# IR_BLASTER_MINI.net
KiCad netlist of a schematic drawn in EAGLE
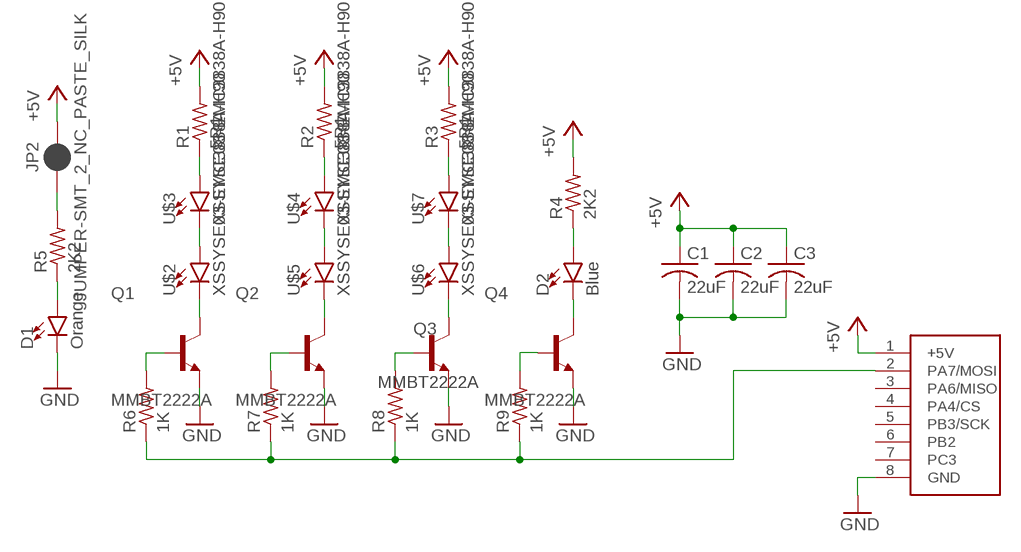
[diagram p0: schematic, sheet 1]

(export (version "E")
  (design (tool "Eeschema 10.0.6"))
  (components
    (comp (ref "C1")
      (value "22uF")
      (footprint "eagle-import:C3216")
      (libsource (lib "eagle-import") (part "C-USC3216"))
    )
    (comp (ref "C2")
      (value "22uF")
      (footprint "eagle-import:C3216")
      (libsource (lib "eagle-import") (part "C-USC3216"))
    )
    (comp (ref "C3")
      (value "22uF")
      (footprint "eagle-import:C3216")
      (libsource (lib "eagle-import") (part "C-USC3216"))
    )
    (comp (ref "D1")
      (value "Orange")
      (footprint "eagle-import:LED-0603")
      (libsource (lib "eagle-import") (part "LED-GREEN0603"))
    )
    (comp (ref "D2")
      (value "Blue")
      (footprint "eagle-import:LED-0603")
      (libsource (lib "eagle-import") (part "LED-BLUE0603"))
    )
    (comp (ref "JP2")
      (value "JUMPER-SMT_2_NC_PASTE_SILK")
      (footprint "eagle-import:SMT-JUMPER_2_NC_PASTE_SILK")
      (libsource (lib "eagle-import") (part "JUMPER-SMT_2_NC_PASTE_SILK"))
    )
    (comp (ref "Q1")
      (value "MMBT2222A")
      (footprint "eagle-import:SOT95P240X120-3N")
      (fields (field (name "MANUFACTURER") "Diotec"))
      (libsource (lib "eagle-import") (part "MMBT2222A"))
    )
    (comp (ref "Q2")
      (value "MMBT2222A")
      (footprint "eagle-import:SOT95P240X120-3N")
      (fields (field (name "MANUFACTURER") "Diotec"))
      (libsource (lib "eagle-import") (part "MMBT2222A"))
    )
    (comp (ref "Q3")
      (value "MMBT2222A")
      (footprint "eagle-import:SOT95P240X120-3N")
      (fields (field (name "MANUFACTURER") "Diotec"))
      (libsource (lib "eagle-import") (part "MMBT2222A"))
    )
    (comp (ref "Q4")
      (value "MMBT2222A")
      (footprint "eagle-import:SOT95P240X120-3N")
      (fields (field (name "MANUFACTURER") "Diotec"))
      (libsource (lib "eagle-import") (part "MMBT2222A"))
    )
    (comp (ref "R1")
      (value "5R1")
      (footprint "eagle-import:R2512")
      (libsource (lib "eagle-import") (part "R-US_R2512"))
    )
    (comp (ref "R2")
      (value "5R1")
      (footprint "eagle-import:R2512")
      (libsource (lib "eagle-import") (part "R-US_R2512"))
    )
    (comp (ref "R3")
      (value "5R1")
      (footprint "eagle-import:R2512")
      (libsource (lib "eagle-import") (part "R-US_R2512"))
    )
    (comp (ref "R4")
      (value "2K2")
      (footprint "eagle-import:R0603")
      (libsource (lib "eagle-import") (part "R-US_R0603"))
    )
    (comp (ref "R5")
      (value "2K2")
      (footprint "eagle-import:R0603")
      (libsource (lib "eagle-import") (part "R-US_R0603"))
    )
    (comp (ref "R6")
      (value "1K")
      (footprint "eagle-import:R0603")
      (libsource (lib "eagle-import") (part "R-US_R0603"))
    )
    (comp (ref "R7")
      (value "1K")
      (footprint "eagle-import:R0603")
      (libsource (lib "eagle-import") (part "R-US_R0603"))
    )
    (comp (ref "R8")
      (value "1K")
      (footprint "eagle-import:R0603")
      (libsource (lib "eagle-import") (part "R-US_R0603"))
    )
    (comp (ref "R9")
      (value "1K")
      (footprint "eagle-import:R0603")
      (libsource (lib "eagle-import") (part "R-US_R0603"))
    )
    (comp (ref "U$1")
      (value "LEFT-H1-SMD")
      (footprint "eagle-import:LEFT-H1-SMD")
      (libsource (lib "eagle-import") (part "LEFT-H1-SMD"))
    )
    (comp (ref "U$2")
      (value "XSSYSE03-EMC3838A-H90")
      (footprint "eagle-import:XSSYSE03-EMC3838A-H90")
      (libsource (lib "eagle-import") (part "XSSYSE03-EMC3838A-H90"))
    )
    (comp (ref "U$3")
      (value "XSSYSE03-EMC3838A-H90")
      (footprint "eagle-import:XSSYSE03-EMC3838A-H90")
      (libsource (lib "eagle-import") (part "XSSYSE03-EMC3838A-H90"))
    )
    (comp (ref "U$4")
      (value "XSSYSE03-EMC3838A-H90")
      (footprint "eagle-import:XSSYSE03-EMC3838A-H90")
      (libsource (lib "eagle-import") (part "XSSYSE03-EMC3838A-H90"))
    )
    (comp (ref "U$5")
      (value "XSSYSE03-EMC3838A-H90")
      (footprint "eagle-import:XSSYSE03-EMC3838A-H90")
      (libsource (lib "eagle-import") (part "XSSYSE03-EMC3838A-H90"))
    )
    (comp (ref "U$6")
      (value "XSSYSE03-EMC3838A-H90")
      (footprint "eagle-import:XSSYSE03-EMC3838A-H90")
      (libsource (lib "eagle-import") (part "XSSYSE03-EMC3838A-H90"))
    )
    (comp (ref "U$7")
      (value "XSSYSE03-EMC3838A-H90")
      (footprint "eagle-import:XSSYSE03-EMC3838A-H90")
      (libsource (lib "eagle-import") (part "XSSYSE03-EMC3838A-H90"))
    )
  )
  (nets
    (net (code "1") (name "+5V") (class "Default")
      (node (ref "C1") (pin "1") (pinfunction "1_1") (pintype "passive"))
      (node (ref "C2") (pin "1") (pinfunction "1_1") (pintype "passive"))
      (node (ref "C3") (pin "1") (pinfunction "1_1") (pintype "passive"))
      (node (ref "JP2") (pin "2") (pinfunction "2_2") (pintype "passive"))
      (node (ref "R1") (pin "2") (pinfunction "2_2") (pintype "passive"))
      (node (ref "R2") (pin "2") (pinfunction "2_2") (pintype "passive"))
      (node (ref "R3") (pin "2") (pinfunction "2_2") (pintype "passive"))
      (node (ref "R4") (pin "2") (pinfunction "2_2") (pintype "passive"))
      (node (ref "U$1") (pin "1") (pinfunction "+5V_1") (pintype "bidirectional"))
    )
    (net (code "2") (name "GND") (class "Default")
      (node (ref "C1") (pin "2") (pinfunction "2_2") (pintype "passive"))
      (node (ref "C2") (pin "2") (pinfunction "2_2") (pintype "passive"))
      (node (ref "C3") (pin "2") (pinfunction "2_2") (pintype "passive"))
      (node (ref "D1") (pin "C") (pinfunction "C_C") (pintype "passive"))
      (node (ref "Q1") (pin "2") (pinfunction "E_2") (pintype "passive"))
      (node (ref "Q2") (pin "2") (pinfunction "E_2") (pintype "passive"))
      (node (ref "Q3") (pin "2") (pinfunction "E_2") (pintype "passive"))
      (node (ref "Q4") (pin "2") (pinfunction "E_2") (pintype "passive"))
      (node (ref "U$1") (pin "8") (pinfunction "GND_8") (pintype "bidirectional"))
    )
    (net (code "3") (name "Net-(D1-PadA)") (class "Default")
      (node (ref "D1") (pin "A") (pinfunction "A_A") (pintype "passive"))
      (node (ref "R5") (pin "1") (pinfunction "1_1") (pintype "passive"))
    )
    (net (code "4") (name "Net-(D2-PadA)") (class "Default")
      (node (ref "D2") (pin "A") (pinfunction "A_A") (pintype "passive"))
      (node (ref "R4") (pin "1") (pinfunction "1_1") (pintype "passive"))
    )
    (net (code "5") (name "Net-(JP2-Pad1)") (class "Default")
      (node (ref "JP2") (pin "1") (pinfunction "1_1") (pintype "passive"))
      (node (ref "R5") (pin "2") (pinfunction "2_2") (pintype "passive"))
    )
    (net (code "6") (name "Net-(Q1-B)") (class "Default")
      (node (ref "Q1") (pin "1") (pinfunction "B_1") (pintype "passive"))
      (node (ref "R6") (pin "2") (pinfunction "2_2") (pintype "passive"))
    )
    (net (code "7") (name "Net-(Q1-C)") (class "Default")
      (node (ref "Q1") (pin "3") (pinfunction "C_3") (pintype "passive"))
      (node (ref "U$2") (pin "P$2") (pinfunction "C_P$2") (pintype "passive"))
    )
    (net (code "8") (name "Net-(Q2-B)") (class "Default")
      (node (ref "Q2") (pin "1") (pinfunction "B_1") (pintype "passive"))
      (node (ref "R7") (pin "2") (pinfunction "2_2") (pintype "passive"))
    )
    (net (code "9") (name "Net-(Q2-C)") (class "Default")
      (node (ref "Q2") (pin "3") (pinfunction "C_3") (pintype "passive"))
      (node (ref "U$5") (pin "P$2") (pinfunction "C_P$2") (pintype "passive"))
    )
    (net (code "10") (name "Net-(Q3-B)") (class "Default")
      (node (ref "Q3") (pin "1") (pinfunction "B_1") (pintype "passive"))
      (node (ref "R8") (pin "2") (pinfunction "2_2") (pintype "passive"))
    )
    (net (code "11") (name "Net-(Q3-C)") (class "Default")
      (node (ref "Q3") (pin "3") (pinfunction "C_3") (pintype "passive"))
      (node (ref "U$6") (pin "P$2") (pinfunction "C_P$2") (pintype "passive"))
    )
    (net (code "12") (name "Net-(Q4-B)") (class "Default")
      (node (ref "Q4") (pin "1") (pinfunction "B_1") (pintype "passive"))
      (node (ref "R9") (pin "2") (pinfunction "2_2") (pintype "passive"))
    )
    (net (code "13") (name "Net-(Q4-C)") (class "Default")
      (node (ref "D2") (pin "C") (pinfunction "C_C") (pintype "passive"))
      (node (ref "Q4") (pin "3") (pinfunction "C_3") (pintype "passive"))
    )
    (net (code "14") (name "Net-(U$1-PA7{slash}MOSI)") (class "Default")
      (node (ref "R6") (pin "1") (pinfunction "1_1") (pintype "passive"))
      (node (ref "R7") (pin "1") (pinfunction "1_1") (pintype "passive"))
      (node (ref "R8") (pin "1") (pinfunction "1_1") (pintype "passive"))
      (node (ref "R9") (pin "1") (pinfunction "1_1") (pintype "passive"))
      (node (ref "U$1") (pin "2") (pinfunction "PA7/MOSI_2") (pintype "bidirectional"))
    )
    (net (code "15") (name "Net-(U$2-A)") (class "Default")
      (node (ref "U$2") (pin "P$1") (pinfunction "A_P$1") (pintype "passive"))
      (node (ref "U$3") (pin "P$2") (pinfunction "C_P$2") (pintype "passive"))
    )
    (net (code "16") (name "Net-(U$3-A)") (class "Default")
      (node (ref "R1") (pin "1") (pinfunction "1_1") (pintype "passive"))
      (node (ref "U$3") (pin "P$1") (pinfunction "A_P$1") (pintype "passive"))
    )
    (net (code "17") (name "Net-(U$4-A)") (class "Default")
      (node (ref "R2") (pin "1") (pinfunction "1_1") (pintype "passive"))
      (node (ref "U$4") (pin "P$1") (pinfunction "A_P$1") (pintype "passive"))
    )
    (net (code "18") (name "Net-(U$4-C)") (class "Default")
      (node (ref "U$4") (pin "P$2") (pinfunction "C_P$2") (pintype "passive"))
      (node (ref "U$5") (pin "P$1") (pinfunction "A_P$1") (pintype "passive"))
    )
    (net (code "19") (name "Net-(U$6-A)") (class "Default")
      (node (ref "U$6") (pin "P$1") (pinfunction "A_P$1") (pintype "passive"))
      (node (ref "U$7") (pin "P$2") (pinfunction "C_P$2") (pintype "passive"))
    )
    (net (code "20") (name "Net-(U$7-A)") (class "Default")
      (node (ref "R3") (pin "1") (pinfunction "1_1") (pintype "passive"))
      (node (ref "U$7") (pin "P$1") (pinfunction "A_P$1") (pintype "passive"))
    )
    (net (code "21") (name "unconnected-(U$1-PA4{slash}CS-Pad4)") (class "Default")
      (node (ref "U$1") (pin "4") (pinfunction "PA4/CS_4") (pintype "bidirectional"))
    )
    (net (code "22") (name "unconnected-(U$1-PA6{slash}MISO-Pad3)") (class "Default")
      (node (ref "U$1") (pin "3") (pinfunction "PA6/MISO_3") (pintype "bidirectional"))
    )
    (net (code "23") (name "unconnected-(U$1-PB2-Pad6)") (class "Default")
      (node (ref "U$1") (pin "6") (pinfunction "PB2_6") (pintype "bidirectional"))
    )
    (net (code "24") (name "unconnected-(U$1-PB3{slash}SCK-Pad5)") (class "Default")
      (node (ref "U$1") (pin "5") (pinfunction "PB3/SCK_5") (pintype "bidirectional"))
    )
    (net (code "25") (name "unconnected-(U$1-PC3-Pad7)") (class "Default")
      (node (ref "U$1") (pin "7") (pinfunction "PC3_7") (pintype "bidirectional"))
    )
  )
)
